# 03__Board_Power.net
KiCad netlist of a schematic drawn in Altium Designer
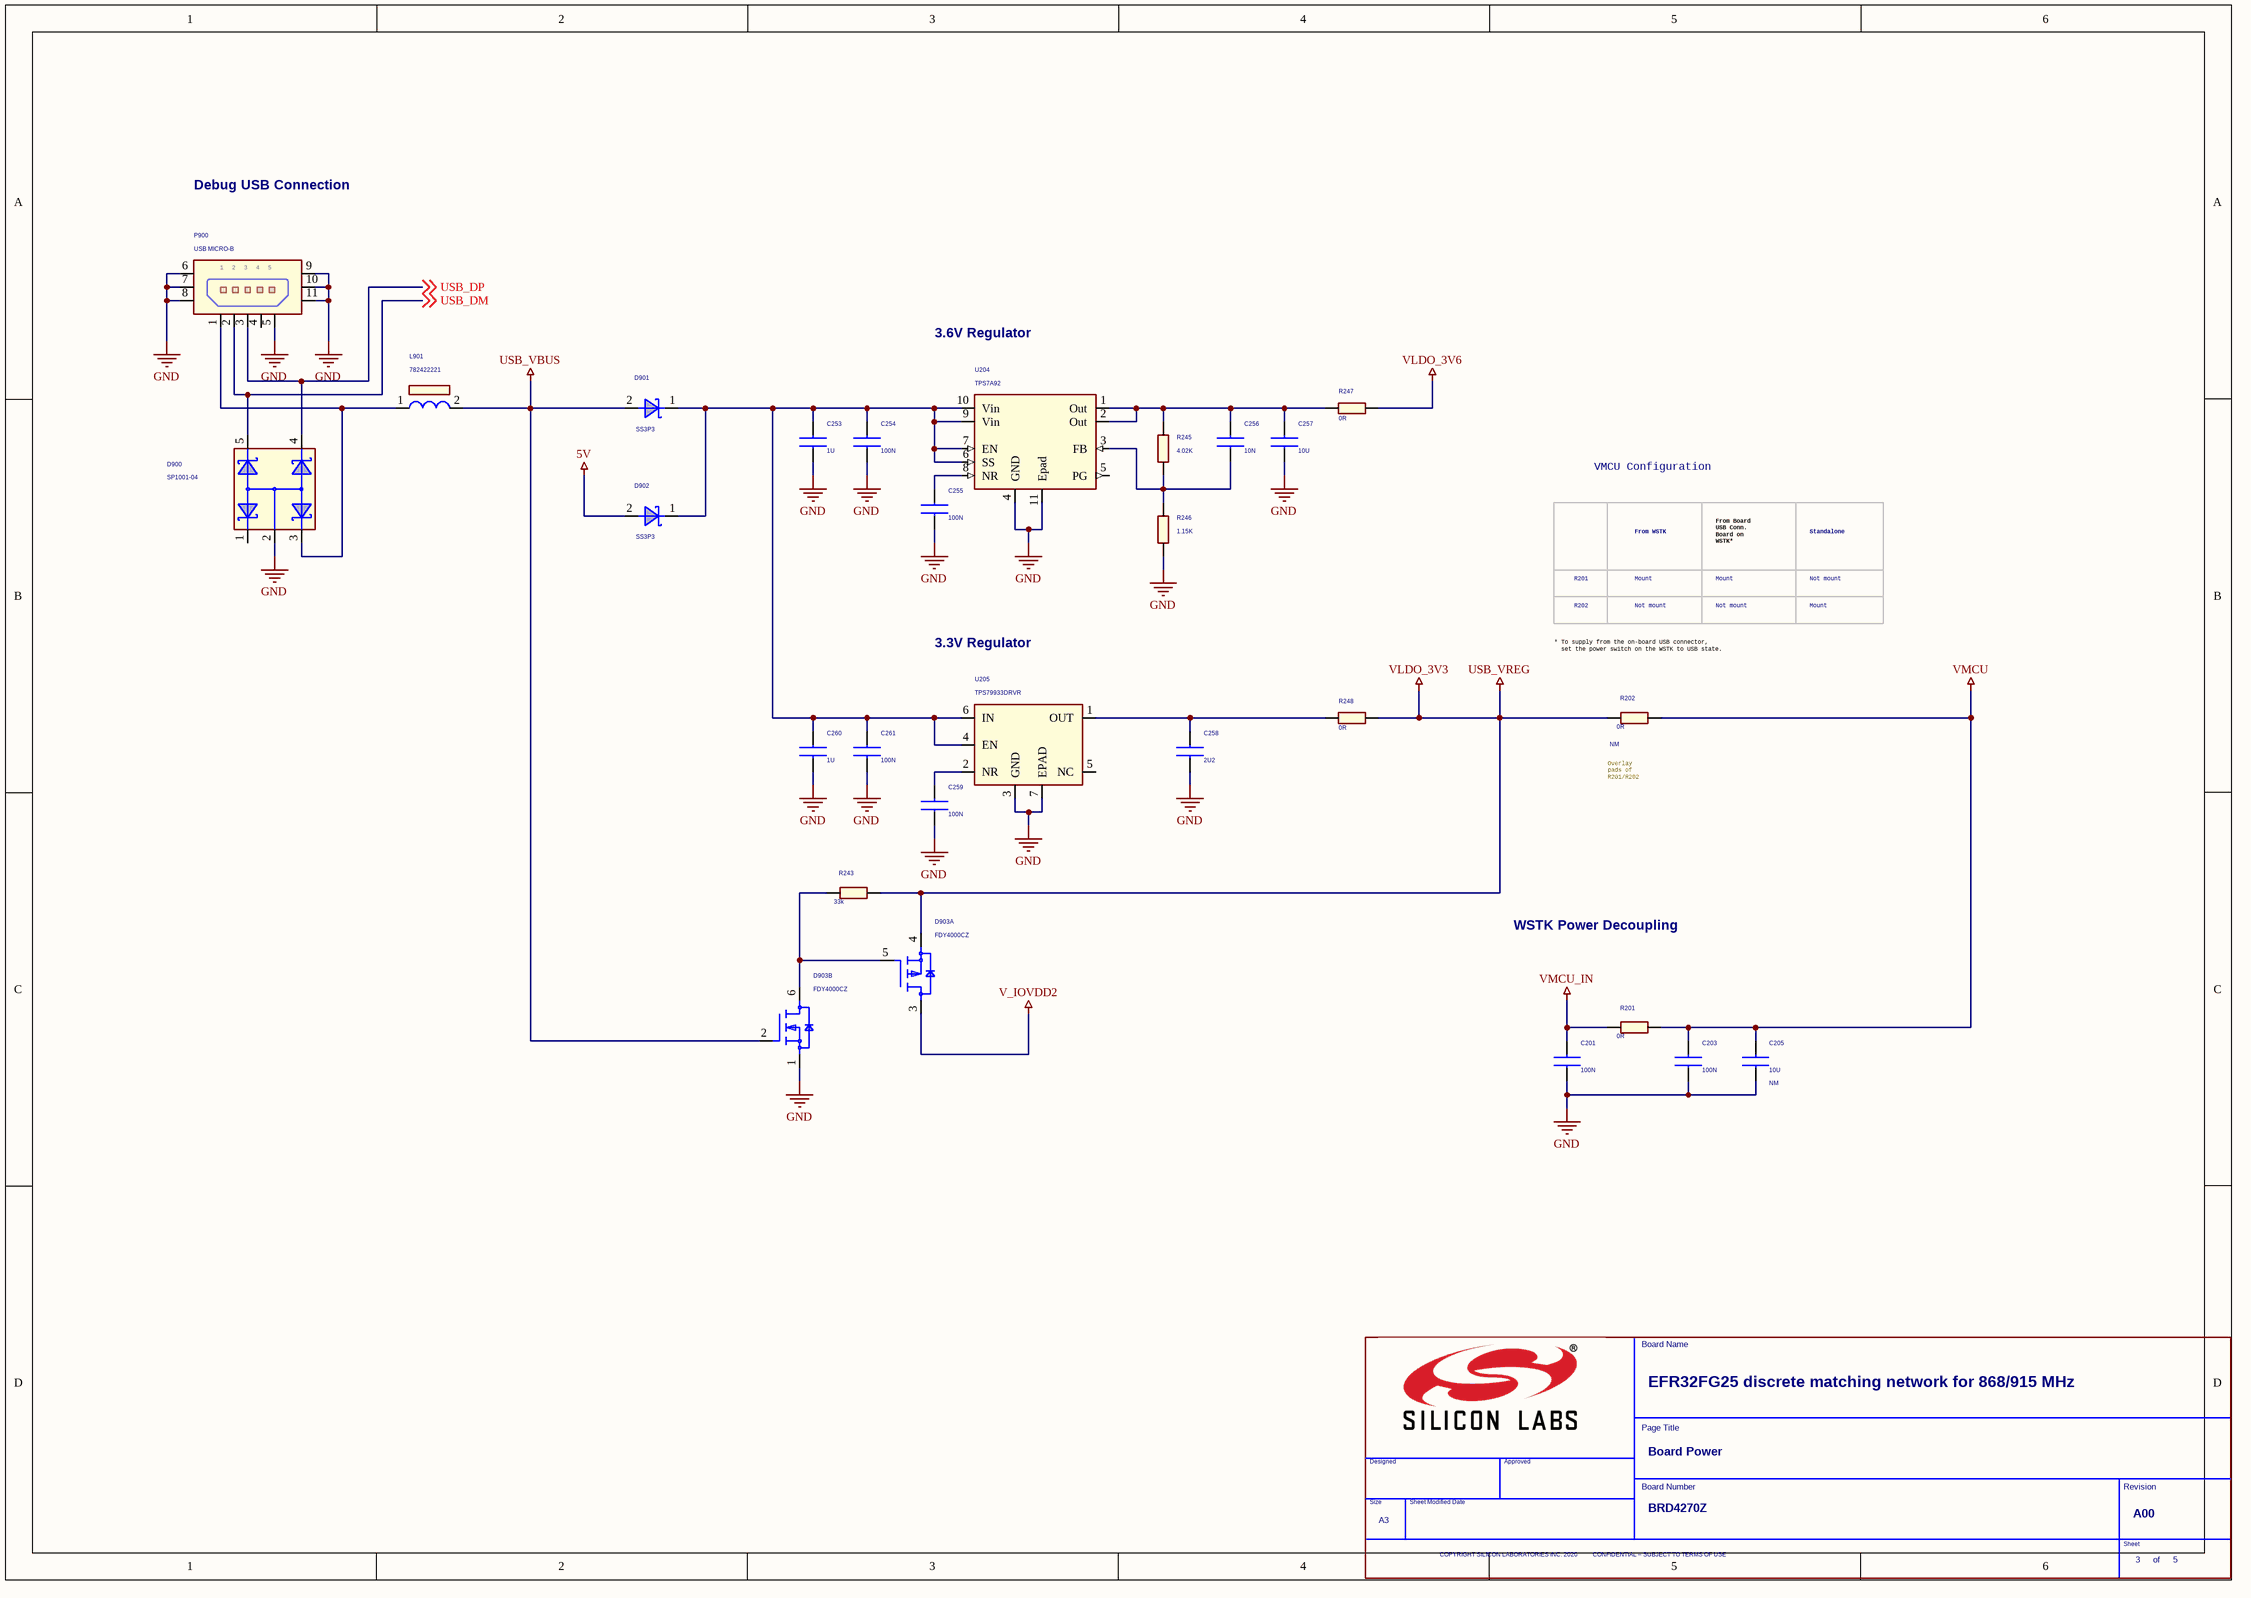
[diagram p0: 03_ Board Power.SchDoc]

(export (version "E")
  (design (tool "Eeschema 10.0.6"))
  (components
    (comp (ref "C201")
      (value "100N")
      (footprint "C0201_L")
      (fields (field (name "TOLERANCE") "20%"))
      (libsource (lib "*") (part "C0201"))
    )
    (comp (ref "C203")
      (value "100N")
      (footprint "C0201_L")
      (fields (field (name "TOLERANCE") "20%"))
      (libsource (lib "*") (part "C0201"))
    )
    (comp (ref "C205")
      (value "10U")
      (footprint "T_UNDEF")
      (fields (field (name "NOT MOUNTED") "NM"))
      (libsource (lib "*") (part "CAPACITOR"))
    )
    (comp (ref "C253")
      (value "1U")
      (footprint "C0402_L")
      (fields (field (name "TOLERANCE") "10%"))
      (libsource (lib "*") (part "C0402"))
    )
    (comp (ref "C254")
      (value "100N")
      (footprint "C0201_L")
      (fields (field (name "TOLERANCE") "20%"))
      (libsource (lib "*") (part "C0201"))
    )
    (comp (ref "C255")
      (value "100N")
      (footprint "C0201_L")
      (fields (field (name "TOLERANCE") "20%"))
      (libsource (lib "*") (part "C0201"))
    )
    (comp (ref "C256")
      (value "10N")
      (footprint "C0201_L")
      (fields (field (name "TOLERANCE") "10%"))
      (libsource (lib "*") (part "C0201"))
    )
    (comp (ref "C257")
      (value "10U")
      (footprint "C0402_L")
      (fields (field (name "TOLERANCE") "20%"))
      (libsource (lib "*") (part "C0402"))
    )
    (comp (ref "C258")
      (value "2U2")
      (footprint "C0402_L")
      (fields (field (name "TOLERANCE") "10%"))
      (libsource (lib "*") (part "C0402"))
    )
    (comp (ref "C259")
      (value "100N")
      (footprint "C0201_L")
      (fields (field (name "TOLERANCE") "20%"))
      (libsource (lib "*") (part "C0201"))
    )
    (comp (ref "C260")
      (value "1U")
      (footprint "C0402_L")
      (fields (field (name "TOLERANCE") "10%"))
      (libsource (lib "*") (part "C0402"))
    )
    (comp (ref "C261")
      (value "100N")
      (footprint "C0201_L")
      (fields (field (name "TOLERANCE") "20%"))
      (libsource (lib "*") (part "C0201"))
    )
    (comp (ref "D900")
      (value "SP1001-04")
      (footprint "SOT553_L")
      (fields (field (name "MFG") "Littlefuse"))
      (libsource (lib "*") (part "SP1001-04"))
    )
    (comp (ref "D901")
      (value "SS3P3")
      (footprint "DO-220AA")
      (fields (field (name "MFG") "Vishay"))
      (libsource (lib "*") (part "SS3P3"))
    )
    (comp (ref "D902")
      (value "SS3P3")
      (footprint "DO-220AA")
      (fields (field (name "MFG") "Vishay"))
      (libsource (lib "*") (part "SS3P3"))
    )
    (comp (ref "D903")
      (value "FDY4000CZ")
      (footprint "SOT-563")
      (fields (field (name "MFG") "ON Semiconductor"))
      (libsource (lib "*") (part "FDY4000CZ"))
    )
    (comp (ref "L901")
      (value "782422221")
      (footprint "COIL_0402")
      (fields (field (name "MFG") "Würth Elektronik"))
      (libsource (lib "*") (part "WE-CBA"))
    )
    (comp (ref "P900")
      (value "USB MICRO-B")
      (footprint "KLS_L-KLS1-238-0-X-0-X")
      (fields (field (name "MFG") "KLS"))
      (libsource (lib "*") (part "KLS L-KLS1-238-0-0-0"))
    )
    (comp (ref "R201") (value "0R") (footprint "R0402_L") (libsource (lib "*") (part "R0402")))
    (comp (ref "R202")
      (value "0R")
      (footprint "R0402_L")
      (fields (field (name "NOT MOUNTED") "NM"))
      (libsource (lib "*") (part "R0402"))
    )
    (comp (ref "R243") (value "33k") (footprint "R0402_L") (libsource (lib "*") (part "R0402")))
    (comp (ref "R245") (value "4.02K") (footprint "R0201_L") (libsource (lib "*") (part "R0201")))
    (comp (ref "R246") (value "1.15K") (footprint "R0201_L") (libsource (lib "*") (part "R0201")))
    (comp (ref "R247") (value "0R") (footprint "R0603_L") (libsource (lib "*") (part "R0603")))
    (comp (ref "R248") (value "0R") (footprint "R0603_L") (libsource (lib "*") (part "R0603")))
    (comp (ref "U204")
      (value "TPS7A92")
      (footprint "WFDFN-10_EP_TPS7A92")
      (fields (field (name "MFG") "Texas Instruments"))
      (libsource (lib "*") (part "TPS7A92"))
    )
    (comp (ref "U205")
      (value "TPS79933DRVR")
      (footprint "SON-6_EP_TPS79933DDCR")
      (fields (field (name "MFG") "Texas Instruments"))
      (libsource (lib "*") (part "TPS79933DRVR"))
    )
  )
  (nets
    (net (code "1") (name "5V") (class "Default")
      (node (ref "D902") (pin "2") (pinfunction "Anode_2") (pintype "passive"))
    )
    (net (code "2") (name "GND") (class "Default")
      (node (ref "C201") (pin "2") (pinfunction "2_2") (pintype "passive"))
      (node (ref "C203") (pin "2") (pinfunction "2_2") (pintype "passive"))
      (node (ref "C205") (pin "2") (pinfunction "2_2") (pintype "passive"))
      (node (ref "C253") (pin "2") (pinfunction "2_2") (pintype "passive"))
      (node (ref "C254") (pin "2") (pinfunction "2_2") (pintype "passive"))
      (node (ref "C255") (pin "2") (pinfunction "2_2") (pintype "passive"))
      (node (ref "C257") (pin "2") (pinfunction "2_2") (pintype "passive"))
      (node (ref "C258") (pin "2") (pinfunction "2_2") (pintype "passive"))
      (node (ref "C259") (pin "2") (pinfunction "2_2") (pintype "passive"))
      (node (ref "C260") (pin "2") (pinfunction "2_2") (pintype "passive"))
      (node (ref "C261") (pin "2") (pinfunction "2_2") (pintype "passive"))
      (node (ref "D900") (pin "2") (pinfunction "2_2") (pintype "passive"))
      (node (ref "D903") (pin "1") (pinfunction "S1_1") (pintype "passive"))
      (node (ref "P900") (pin "10") (pinfunction "10_10") (pintype "passive"))
      (node (ref "P900") (pin "11") (pinfunction "11_11") (pintype "passive"))
      (node (ref "P900") (pin "5") (pinfunction "5_5") (pintype "passive"))
      (node (ref "P900") (pin "6") (pinfunction "6_6") (pintype "passive"))
      (node (ref "P900") (pin "7") (pinfunction "7_7") (pintype "passive"))
      (node (ref "P900") (pin "8") (pinfunction "8_8") (pintype "passive"))
      (node (ref "P900") (pin "9") (pinfunction "9_9") (pintype "passive"))
      (node (ref "R246") (pin "1") (pinfunction "1_1") (pintype "passive"))
      (node (ref "U204") (pin "11") (pinfunction "Epad_11") (pintype "power_in"))
      (node (ref "U204") (pin "4") (pinfunction "GND_4") (pintype "power_in"))
      (node (ref "U205") (pin "3") (pinfunction "GND_3") (pintype "passive"))
      (node (ref "U205") (pin "7") (pinfunction "EPAD_7") (pintype "passive"))
    )
    (net (code "3") (name "Net-(C256-Pad1)") (class "Default")
      (node (ref "C256") (pin "1") (pinfunction "1_1") (pintype "passive"))
      (node (ref "C257") (pin "1") (pinfunction "1_1") (pintype "passive"))
      (node (ref "R245") (pin "2") (pinfunction "2_2") (pintype "passive"))
      (node (ref "R247") (pin "1") (pinfunction "1_1") (pintype "passive"))
      (node (ref "U204") (pin "1") (pinfunction "Out_1") (pintype "power_in"))
      (node (ref "U204") (pin "2") (pinfunction "Out_2") (pintype "power_in"))
    )
    (net (code "4") (name "Net-(D900-Pad3)") (class "Default")
      (node (ref "D900") (pin "3") (pinfunction "3_3") (pintype "passive"))
      (node (ref "L901") (pin "1") (pinfunction "1_1") (pintype "passive"))
      (node (ref "P900") (pin "1") (pinfunction "1_1") (pintype "passive"))
    )
    (net (code "5") (name "Net-(D901-Cathode)") (class "Default")
      (node (ref "C253") (pin "1") (pinfunction "1_1") (pintype "passive"))
      (node (ref "C254") (pin "1") (pinfunction "1_1") (pintype "passive"))
      (node (ref "C260") (pin "1") (pinfunction "1_1") (pintype "passive"))
      (node (ref "C261") (pin "1") (pinfunction "1_1") (pintype "passive"))
      (node (ref "D901") (pin "1") (pinfunction "Cathode_1") (pintype "passive"))
      (node (ref "D902") (pin "1") (pinfunction "Cathode_1") (pintype "passive"))
      (node (ref "U204") (pin "10") (pinfunction "Vin_10") (pintype "power_in"))
      (node (ref "U204") (pin "6") (pinfunction "SS_6") (pintype "input"))
      (node (ref "U204") (pin "7") (pinfunction "EN_7") (pintype "input"))
      (node (ref "U204") (pin "9") (pinfunction "Vin_9") (pintype "power_in"))
      (node (ref "U205") (pin "4") (pinfunction "EN_4") (pintype "passive"))
      (node (ref "U205") (pin "6") (pinfunction "IN_6") (pintype "passive"))
    )
    (net (code "6") (name "Net-(D903A-G5)") (class "Default")
      (node (ref "D903") (pin "5") (pinfunction "G5_5") (pintype "passive"))
      (node (ref "D903") (pin "6") (pinfunction "D1_6") (pintype "passive"))
      (node (ref "R243") (pin "2") (pinfunction "2_2") (pintype "passive"))
    )
    (net (code "7") (name "Net-(U204-FB)") (class "Default")
      (node (ref "C256") (pin "2") (pinfunction "2_2") (pintype "passive"))
      (node (ref "R245") (pin "1") (pinfunction "1_1") (pintype "passive"))
      (node (ref "R246") (pin "2") (pinfunction "2_2") (pintype "passive"))
      (node (ref "U204") (pin "3") (pinfunction "FB_3") (pintype "input"))
    )
    (net (code "8") (name "Net-(U204-NR)") (class "Default")
      (node (ref "C255") (pin "1") (pinfunction "1_1") (pintype "passive"))
      (node (ref "U204") (pin "8") (pinfunction "NR_8") (pintype "input"))
    )
    (net (code "9") (name "Net-(U205-NR)") (class "Default")
      (node (ref "C259") (pin "1") (pinfunction "1_1") (pintype "passive"))
      (node (ref "U205") (pin "2") (pinfunction "NR_2") (pintype "passive"))
    )
    (net (code "10") (name "Net-(U205-OUT)") (class "Default")
      (node (ref "C258") (pin "1") (pinfunction "1_1") (pintype "passive"))
      (node (ref "R248") (pin "1") (pinfunction "1_1") (pintype "passive"))
      (node (ref "U205") (pin "1") (pinfunction "OUT_1") (pintype "passive"))
    )
    (net (code "11") (name "USB_DM") (class "Default")
      (node (ref "D900") (pin "5") (pinfunction "5_5") (pintype "passive"))
      (node (ref "P900") (pin "2") (pinfunction "2_2") (pintype "passive"))
    )
    (net (code "12") (name "USB_DP") (class "Default")
      (node (ref "D900") (pin "4") (pinfunction "4_4") (pintype "passive"))
      (node (ref "P900") (pin "3") (pinfunction "3_3") (pintype "passive"))
    )
    (net (code "13") (name "USB_VBUS") (class "Default")
      (node (ref "D901") (pin "2") (pinfunction "Anode_2") (pintype "passive"))
      (node (ref "D903") (pin "2") (pinfunction "G1_2") (pintype "passive"))
      (node (ref "L901") (pin "2") (pinfunction "2_2") (pintype "passive"))
    )
    (net (code "14") (name "USB_VREG") (class "Default")
      (node (ref "D903") (pin "4") (pinfunction "S2_4") (pintype "passive"))
      (node (ref "R202") (pin "2") (pinfunction "2_2") (pintype "passive"))
      (node (ref "R243") (pin "1") (pinfunction "1_1") (pintype "passive"))
      (node (ref "R248") (pin "2") (pinfunction "2_2") (pintype "passive"))
    )
    (net (code "15") (name "VLDO_3V6") (class "Default")
      (node (ref "R247") (pin "2") (pinfunction "2_2") (pintype "passive"))
    )
    (net (code "16") (name "VMCU") (class "Default")
      (node (ref "C203") (pin "1") (pinfunction "1_1") (pintype "passive"))
      (node (ref "C205") (pin "1") (pinfunction "1_1") (pintype "passive"))
      (node (ref "R201") (pin "1") (pinfunction "1_1") (pintype "passive"))
      (node (ref "R202") (pin "1") (pinfunction "1_1") (pintype "passive"))
    )
    (net (code "17") (name "VMCU_IN") (class "Default")
      (node (ref "C201") (pin "1") (pinfunction "1_1") (pintype "passive"))
      (node (ref "R201") (pin "2") (pinfunction "2_2") (pintype "passive"))
    )
    (net (code "18") (name "V_IOVDD2") (class "Default")
      (node (ref "D903") (pin "3") (pinfunction "D2_3") (pintype "passive"))
    )
    (net (code "19") (name "unconnected-(D900-Pad1)") (class "Default")
      (node (ref "D900") (pin "1") (pinfunction "1_1") (pintype "passive"))
    )
    (net (code "20") (name "unconnected-(P900-Pad4)") (class "Default")
      (node (ref "P900") (pin "4") (pinfunction "4_4") (pintype "passive"))
    )
    (net (code "21") (name "unconnected-(U204-PG-Pad5)") (class "Default")
      (node (ref "U204") (pin "5") (pinfunction "PG_5") (pintype "output"))
    )
    (net (code "22") (name "unconnected-(U205-NC-Pad5)") (class "Default")
      (node (ref "U205") (pin "5") (pinfunction "NC_5") (pintype "passive"))
    )
  )
)
